# Top_Level.net
KiCad netlist of a schematic drawn in Altium Designer
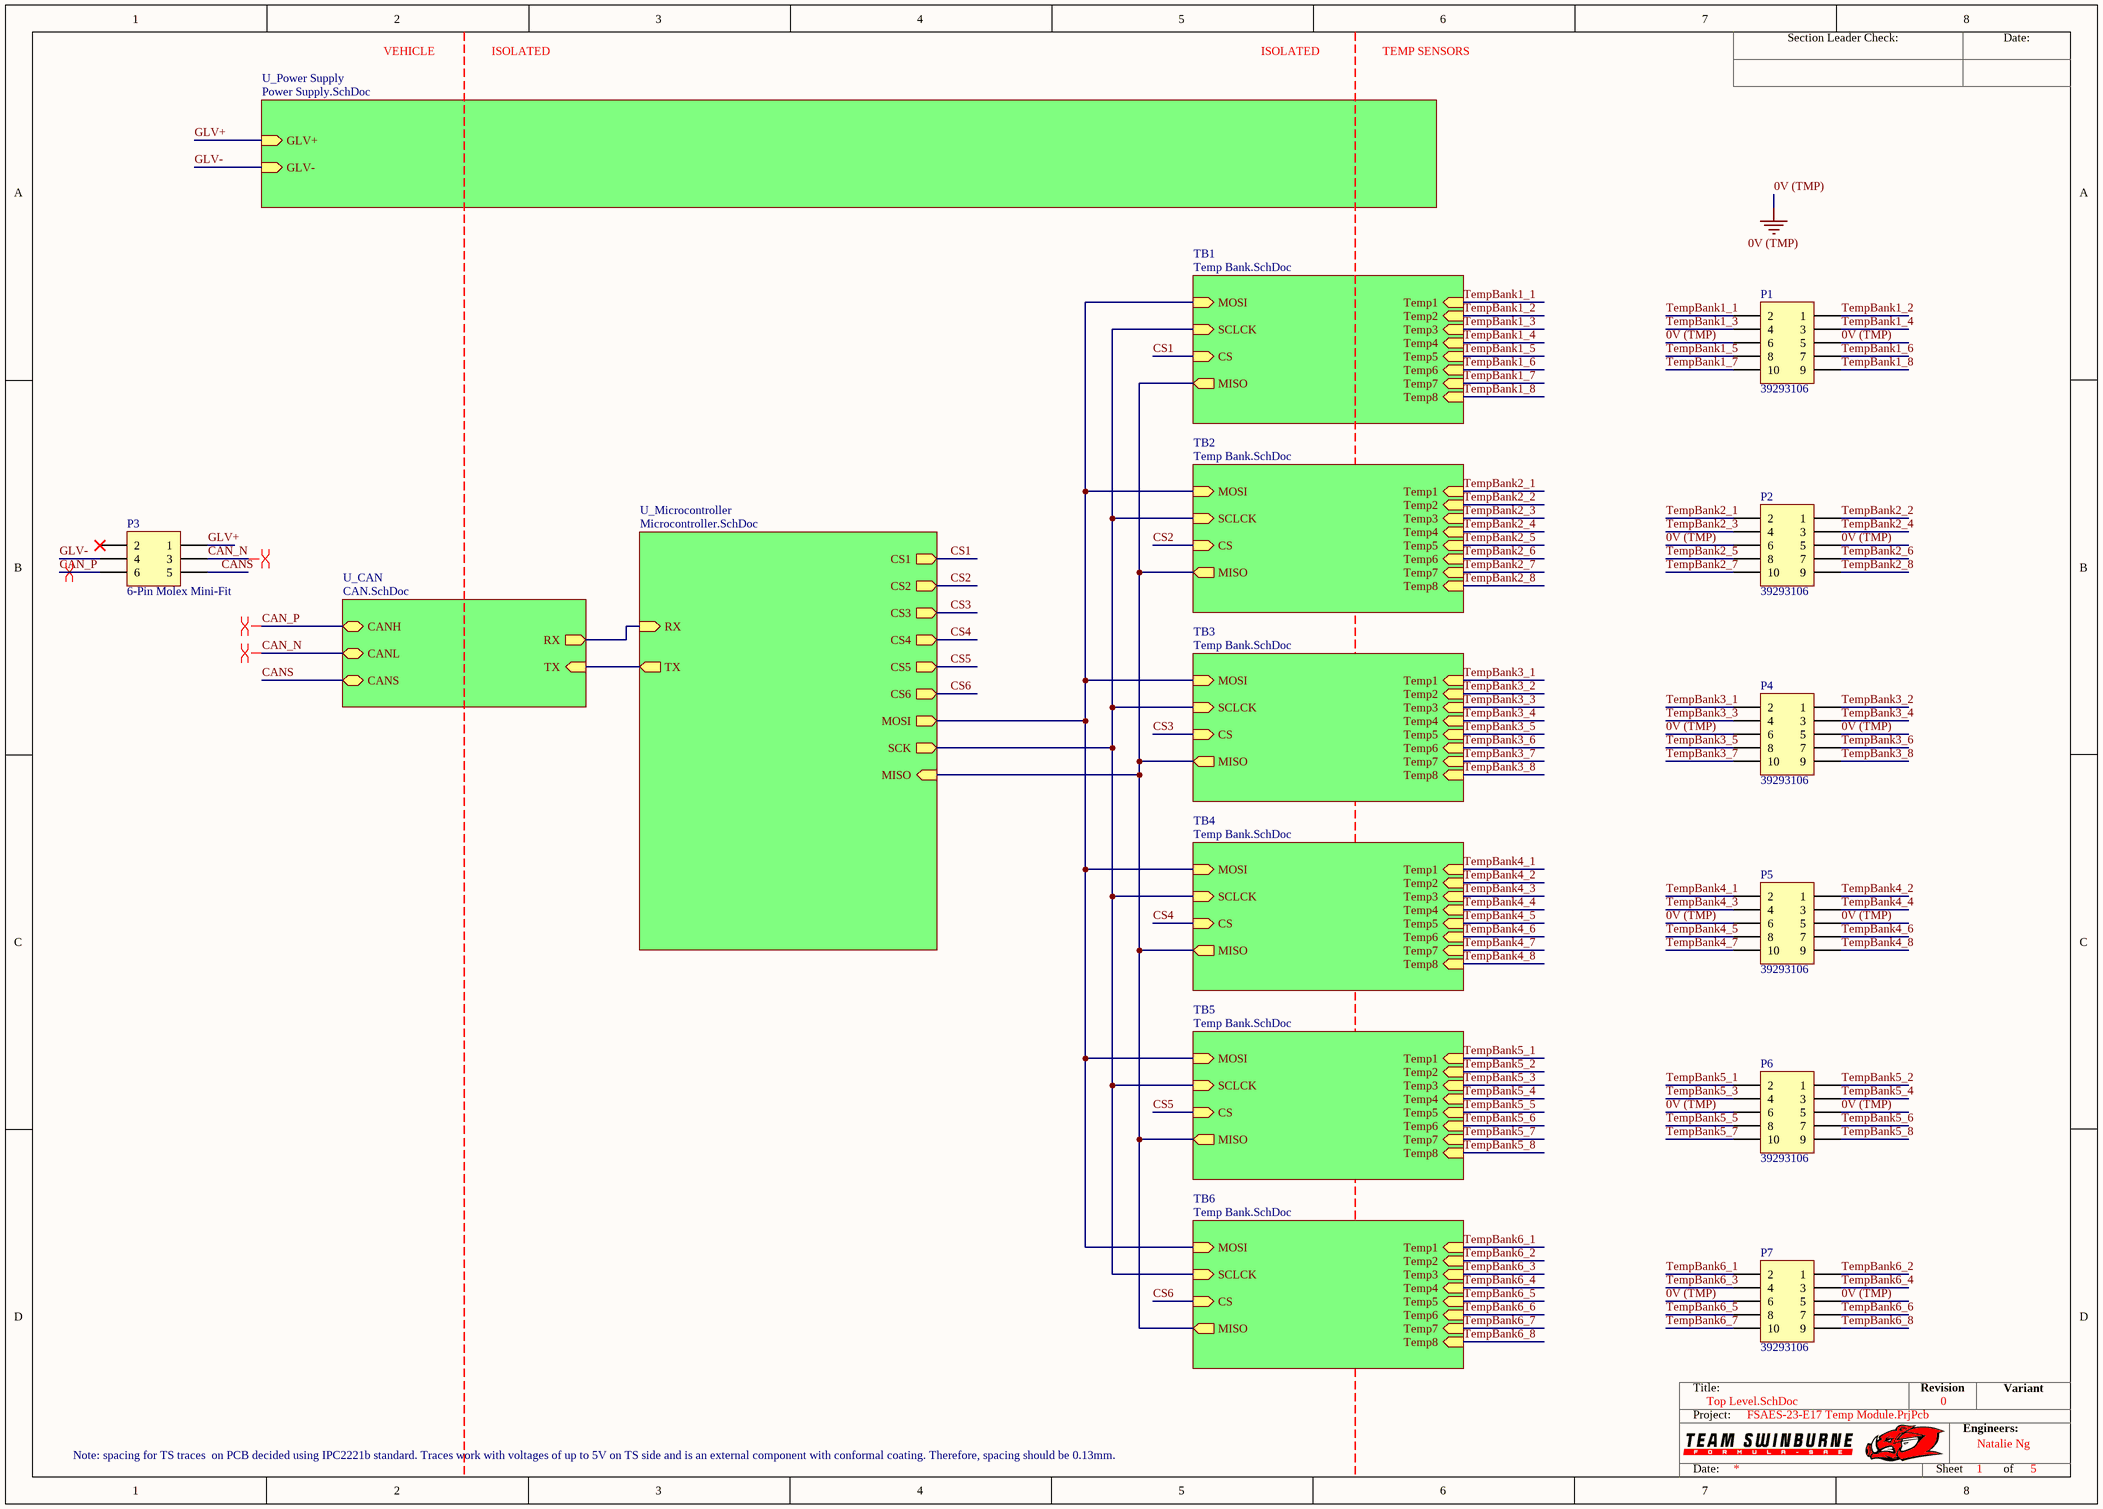
[diagram p0: Top Level.SchDoc]

(export (version "E")
  (design (tool "Eeschema 10.0.6"))
  (components
    (comp (ref "P1")
      (value "39293106")
      (footprint "39293106")
      (fields (field (name "DIGIKEY PART NUMBER") "WM3847-ND") (field (name "CONTACT") "Tin"))
      (libsource (lib "ts_20-standard-connectors") (part "10"))
    )
    (comp (ref "P2")
      (value "39293106")
      (footprint "39293106")
      (fields (field (name "DIGIKEY PART NUMBER") "WM3847-ND") (field (name "CONTACT") "Tin"))
      (libsource (lib "ts_20-standard-connectors") (part "10"))
    )
    (comp (ref "P3")
      (value "6-Pin Molex Mini-Fit")
      (footprint "6-Pin Molex Mini-Fit")
      (description "6-Pin Molex Mini-Fit Connector Header 6 pin mini fit")
      (libsource (lib "Team Swinburne") (part "3x2-Pin connector"))
    )
    (comp (ref "P4")
      (value "39293106")
      (footprint "39293106")
      (fields (field (name "DIGIKEY PART NUMBER") "WM3847-ND") (field (name "CONTACT") "Tin"))
      (libsource (lib "ts_20-standard-connectors") (part "10"))
    )
    (comp (ref "P5")
      (value "39293106")
      (footprint "39293106")
      (fields (field (name "DIGIKEY PART NUMBER") "WM3847-ND") (field (name "CONTACT") "Tin"))
      (libsource (lib "ts_20-standard-connectors") (part "10"))
    )
    (comp (ref "P6")
      (value "39293106")
      (footprint "39293106")
      (fields (field (name "DIGIKEY PART NUMBER") "WM3847-ND") (field (name "CONTACT") "Tin"))
      (libsource (lib "ts_20-standard-connectors") (part "10"))
    )
    (comp (ref "P7")
      (value "39293106")
      (footprint "39293106")
      (fields (field (name "DIGIKEY PART NUMBER") "WM3847-ND") (field (name "CONTACT") "Tin"))
      (libsource (lib "ts_20-standard-connectors") (part "10"))
    )
  )
  (nets
    (net (code "2") (name "/CANS") (class "Default")
      (node (ref "P3") (pin "5") (pinfunction "5_5") (pintype "passive"))
    )
    (net (code "3") (name "/CAN_N") (class "Default")
      (node (ref "P3") (pin "3") (pinfunction "3_3") (pintype "passive"))
    )
    (net (code "4") (name "/CAN_P") (class "Default")
      (node (ref "P3") (pin "6") (pinfunction "6_6") (pintype "passive"))
    )
    (net (code "11") (name "/GLV+") (class "Default")
      (node (ref "P3") (pin "1") (pinfunction "1_1") (pintype "passive"))
    )
    (net (code "12") (name "/GLV-") (class "Default")
      (node (ref "P3") (pin "4") (pinfunction "4_4") (pintype "passive"))
    )
    (net (code "18") (name "/TempBank1_1") (class "Default")
      (node (ref "P1") (pin "2") (pinfunction "2_2") (pintype "passive"))
    )
    (net (code "19") (name "/TempBank1_2") (class "Default")
      (node (ref "P1") (pin "1") (pinfunction "1_1") (pintype "passive"))
    )
    (net (code "20") (name "/TempBank1_3") (class "Default")
      (node (ref "P1") (pin "4") (pinfunction "4_4") (pintype "passive"))
    )
    (net (code "21") (name "/TempBank1_4") (class "Default")
      (node (ref "P1") (pin "3") (pinfunction "3_3") (pintype "passive"))
    )
    (net (code "22") (name "/TempBank1_5") (class "Default")
      (node (ref "P1") (pin "8") (pinfunction "8_8") (pintype "passive"))
    )
    (net (code "23") (name "/TempBank1_6") (class "Default")
      (node (ref "P1") (pin "7") (pinfunction "7_7") (pintype "passive"))
    )
    (net (code "24") (name "/TempBank1_7") (class "Default")
      (node (ref "P1") (pin "10") (pinfunction "10_10") (pintype "passive"))
    )
    (net (code "25") (name "/TempBank1_8") (class "Default")
      (node (ref "P1") (pin "9") (pinfunction "9_9") (pintype "passive"))
    )
    (net (code "26") (name "/TempBank2_1") (class "Default")
      (node (ref "P2") (pin "2") (pinfunction "2_2") (pintype "passive"))
    )
    (net (code "27") (name "/TempBank2_2") (class "Default")
      (node (ref "P2") (pin "1") (pinfunction "1_1") (pintype "passive"))
    )
    (net (code "28") (name "/TempBank2_3") (class "Default")
      (node (ref "P2") (pin "4") (pinfunction "4_4") (pintype "passive"))
    )
    (net (code "29") (name "/TempBank2_4") (class "Default")
      (node (ref "P2") (pin "3") (pinfunction "3_3") (pintype "passive"))
    )
    (net (code "30") (name "/TempBank2_5") (class "Default")
      (node (ref "P2") (pin "8") (pinfunction "8_8") (pintype "passive"))
    )
    (net (code "31") (name "/TempBank2_6") (class "Default")
      (node (ref "P2") (pin "7") (pinfunction "7_7") (pintype "passive"))
    )
    (net (code "32") (name "/TempBank2_7") (class "Default")
      (node (ref "P2") (pin "10") (pinfunction "10_10") (pintype "passive"))
    )
    (net (code "33") (name "/TempBank2_8") (class "Default")
      (node (ref "P2") (pin "9") (pinfunction "9_9") (pintype "passive"))
    )
    (net (code "34") (name "/TempBank3_1") (class "Default")
      (node (ref "P4") (pin "2") (pinfunction "2_2") (pintype "passive"))
    )
    (net (code "35") (name "/TempBank3_2") (class "Default")
      (node (ref "P4") (pin "1") (pinfunction "1_1") (pintype "passive"))
    )
    (net (code "36") (name "/TempBank3_3") (class "Default")
      (node (ref "P4") (pin "4") (pinfunction "4_4") (pintype "passive"))
    )
    (net (code "37") (name "/TempBank3_4") (class "Default")
      (node (ref "P4") (pin "3") (pinfunction "3_3") (pintype "passive"))
    )
    (net (code "38") (name "/TempBank3_5") (class "Default")
      (node (ref "P4") (pin "8") (pinfunction "8_8") (pintype "passive"))
    )
    (net (code "39") (name "/TempBank3_6") (class "Default")
      (node (ref "P4") (pin "7") (pinfunction "7_7") (pintype "passive"))
    )
    (net (code "40") (name "/TempBank3_7") (class "Default")
      (node (ref "P4") (pin "10") (pinfunction "10_10") (pintype "passive"))
    )
    (net (code "41") (name "/TempBank3_8") (class "Default")
      (node (ref "P4") (pin "9") (pinfunction "9_9") (pintype "passive"))
    )
    (net (code "42") (name "/TempBank4_1") (class "Default")
      (node (ref "P5") (pin "2") (pinfunction "2_2") (pintype "passive"))
    )
    (net (code "43") (name "/TempBank4_2") (class "Default")
      (node (ref "P5") (pin "1") (pinfunction "1_1") (pintype "passive"))
    )
    (net (code "44") (name "/TempBank4_3") (class "Default")
      (node (ref "P5") (pin "4") (pinfunction "4_4") (pintype "passive"))
    )
    (net (code "45") (name "/TempBank4_4") (class "Default")
      (node (ref "P5") (pin "3") (pinfunction "3_3") (pintype "passive"))
    )
    (net (code "46") (name "/TempBank4_5") (class "Default")
      (node (ref "P5") (pin "8") (pinfunction "8_8") (pintype "passive"))
    )
    (net (code "47") (name "/TempBank4_6") (class "Default")
      (node (ref "P5") (pin "7") (pinfunction "7_7") (pintype "passive"))
    )
    (net (code "48") (name "/TempBank4_7") (class "Default")
      (node (ref "P5") (pin "10") (pinfunction "10_10") (pintype "passive"))
    )
    (net (code "49") (name "/TempBank4_8") (class "Default")
      (node (ref "P5") (pin "9") (pinfunction "9_9") (pintype "passive"))
    )
    (net (code "50") (name "/TempBank5_1") (class "Default")
      (node (ref "P6") (pin "2") (pinfunction "2_2") (pintype "passive"))
    )
    (net (code "51") (name "/TempBank5_2") (class "Default")
      (node (ref "P6") (pin "1") (pinfunction "1_1") (pintype "passive"))
    )
    (net (code "52") (name "/TempBank5_3") (class "Default")
      (node (ref "P6") (pin "4") (pinfunction "4_4") (pintype "passive"))
    )
    (net (code "53") (name "/TempBank5_4") (class "Default")
      (node (ref "P6") (pin "3") (pinfunction "3_3") (pintype "passive"))
    )
    (net (code "54") (name "/TempBank5_5") (class "Default")
      (node (ref "P6") (pin "8") (pinfunction "8_8") (pintype "passive"))
    )
    (net (code "55") (name "/TempBank5_6") (class "Default")
      (node (ref "P6") (pin "7") (pinfunction "7_7") (pintype "passive"))
    )
    (net (code "56") (name "/TempBank5_7") (class "Default")
      (node (ref "P6") (pin "10") (pinfunction "10_10") (pintype "passive"))
    )
    (net (code "57") (name "/TempBank5_8") (class "Default")
      (node (ref "P6") (pin "9") (pinfunction "9_9") (pintype "passive"))
    )
    (net (code "58") (name "/TempBank6_1") (class "Default")
      (node (ref "P7") (pin "2") (pinfunction "2_2") (pintype "passive"))
    )
    (net (code "59") (name "/TempBank6_2") (class "Default")
      (node (ref "P7") (pin "1") (pinfunction "1_1") (pintype "passive"))
    )
    (net (code "60") (name "/TempBank6_3") (class "Default")
      (node (ref "P7") (pin "4") (pinfunction "4_4") (pintype "passive"))
    )
    (net (code "61") (name "/TempBank6_4") (class "Default")
      (node (ref "P7") (pin "3") (pinfunction "3_3") (pintype "passive"))
    )
    (net (code "62") (name "/TempBank6_5") (class "Default")
      (node (ref "P7") (pin "8") (pinfunction "8_8") (pintype "passive"))
    )
    (net (code "63") (name "/TempBank6_6") (class "Default")
      (node (ref "P7") (pin "7") (pinfunction "7_7") (pintype "passive"))
    )
    (net (code "64") (name "/TempBank6_7") (class "Default")
      (node (ref "P7") (pin "10") (pinfunction "10_10") (pintype "passive"))
    )
    (net (code "65") (name "/TempBank6_8") (class "Default")
      (node (ref "P7") (pin "9") (pinfunction "9_9") (pintype "passive"))
    )
    (net (code "66") (name "0V (TMP)") (class "Default")
      (node (ref "P1") (pin "5") (pinfunction "5_5") (pintype "passive"))
      (node (ref "P1") (pin "6") (pinfunction "6_6") (pintype "passive"))
      (node (ref "P2") (pin "5") (pinfunction "5_5") (pintype "passive"))
      (node (ref "P2") (pin "6") (pinfunction "6_6") (pintype "passive"))
      (node (ref "P4") (pin "5") (pinfunction "5_5") (pintype "passive"))
      (node (ref "P4") (pin "6") (pinfunction "6_6") (pintype "passive"))
      (node (ref "P5") (pin "5") (pinfunction "5_5") (pintype "passive"))
      (node (ref "P5") (pin "6") (pinfunction "6_6") (pintype "passive"))
      (node (ref "P6") (pin "5") (pinfunction "5_5") (pintype "passive"))
      (node (ref "P6") (pin "6") (pinfunction "6_6") (pintype "passive"))
      (node (ref "P7") (pin "5") (pinfunction "5_5") (pintype "passive"))
      (node (ref "P7") (pin "6") (pinfunction "6_6") (pintype "passive"))
    )
    (net (code "67") (name "unconnected-(P3-Pad2)") (class "Default")
      (node (ref "P3") (pin "2") (pinfunction "2_2") (pintype "passive+no_connect"))
    )
  )
)
